# T03_MotionControledLampNFET.net
KiCad netlist of a schematic drawn in EAGLE
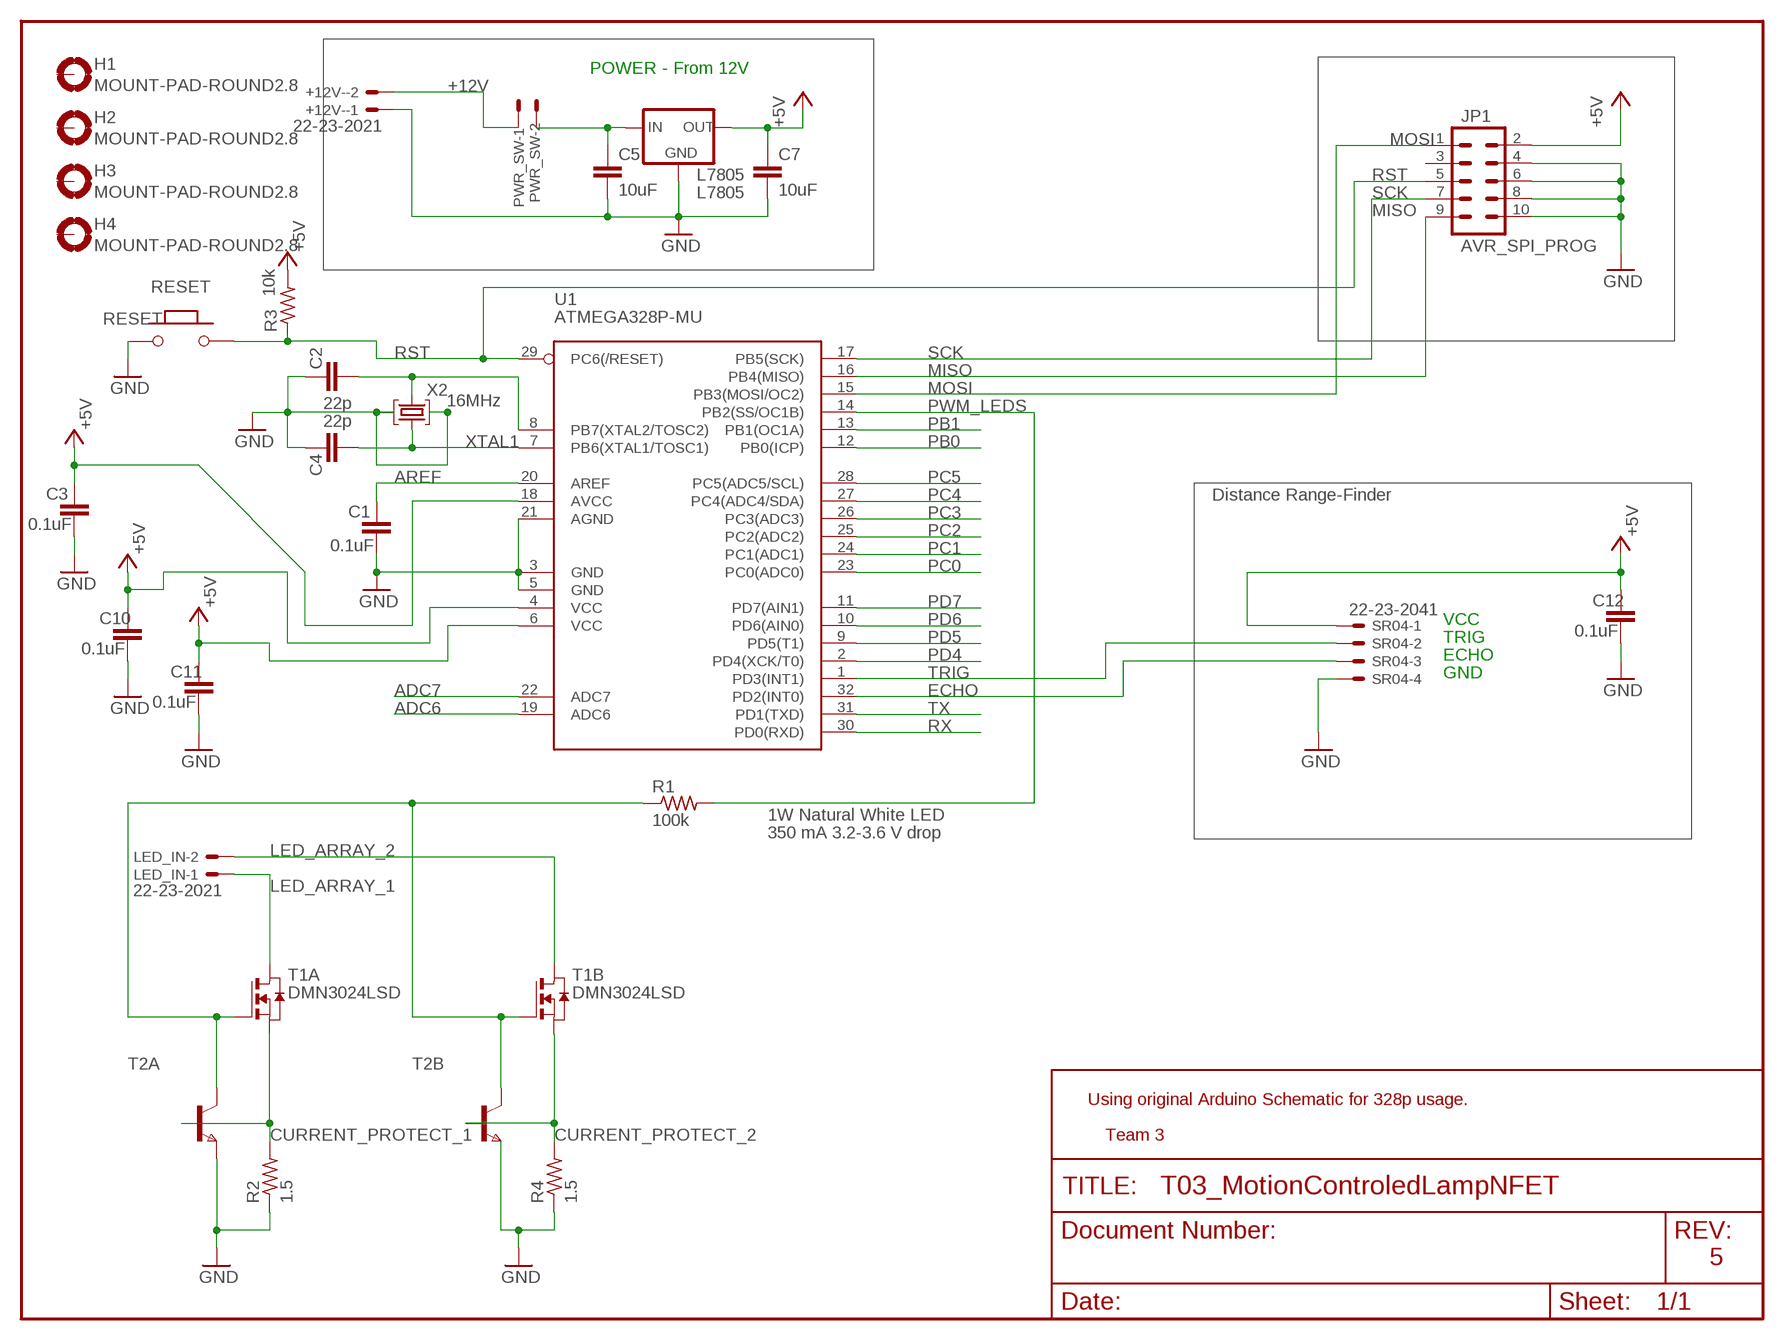
[diagram p0: schematic, sheet 1]

(export (version "E")
  (design (tool "Eeschema 10.0.6"))
  (components
    (comp (ref "+12V-")
      (value "22-23-2021")
      (footprint "eagle-import:22-23-2021")
      (fields (field (name "MF") "MOLEX"))
      (libsource (lib "eagle-import") (part "22-23-2021"))
    )
    (comp (ref "C1")
      (value "0.1uF")
      (footprint "eagle-import:C0603-ROUND")
      (libsource (lib "eagle-import") (part "C-EUC0603"))
    )
    (comp (ref "C2")
      (value "22p")
      (footprint "eagle-import:C0603-ROUND")
      (libsource (lib "eagle-import") (part "C-EUC0603"))
    )
    (comp (ref "C3")
      (value "0.1uF")
      (footprint "eagle-import:C0603-ROUND")
      (libsource (lib "eagle-import") (part "C-EUC0603"))
    )
    (comp (ref "C4")
      (value "22p")
      (footprint "eagle-import:C0603-ROUND")
      (libsource (lib "eagle-import") (part "C-EUC0603"))
    )
    (comp (ref "C5")
      (value "10uF")
      (footprint "eagle-import:C1206")
      (libsource (lib "eagle-import") (part "rcl_C-EUC1206"))
    )
    (comp (ref "C7")
      (value "10uF")
      (footprint "eagle-import:C1206")
      (libsource (lib "eagle-import") (part "rcl_C-EUC1206"))
    )
    (comp (ref "C10")
      (value "0.1uF")
      (footprint "eagle-import:C0603-ROUND")
      (libsource (lib "eagle-import") (part "C-EUC0603"))
    )
    (comp (ref "C11")
      (value "0.1uF")
      (footprint "eagle-import:C0603-ROUND")
      (libsource (lib "eagle-import") (part "C-EUC0603"))
    )
    (comp (ref "C12")
      (value "0.1uF")
      (footprint "eagle-import:C0603-ROUND")
      (libsource (lib "eagle-import") (part "C-EUC0603"))
    )
    (comp (ref "H1")
      (value "MOUNT-PAD-ROUND2.8")
      (footprint "eagle-import:2,8-PAD")
      (libsource (lib "eagle-import") (part "MOUNT-PAD-ROUND2.8"))
    )
    (comp (ref "H2")
      (value "MOUNT-PAD-ROUND2.8")
      (footprint "eagle-import:2,8-PAD")
      (libsource (lib "eagle-import") (part "MOUNT-PAD-ROUND2.8"))
    )
    (comp (ref "H3")
      (value "MOUNT-PAD-ROUND2.8")
      (footprint "eagle-import:2,8-PAD")
      (libsource (lib "eagle-import") (part "MOUNT-PAD-ROUND2.8"))
    )
    (comp (ref "H4")
      (value "MOUNT-PAD-ROUND2.8")
      (footprint "eagle-import:2,8-PAD")
      (libsource (lib "eagle-import") (part "MOUNT-PAD-ROUND2.8"))
    )
    (comp (ref "JP1")
      (value "AVR_SPI_PROG")
      (footprint "eagle-import:2X5-SHROUDED_LOCK")
      (libsource (lib "eagle-import") (part "M05X2SHD_LOCK"))
    )
    (comp (ref "L7805")
      (value "L7805")
      (footprint "eagle-import:78XXL")
      (libsource (lib "eagle-import") (part "78XXL"))
    )
    (comp (ref "LED_IN")
      (value "22-23-2021")
      (footprint "eagle-import:22-23-2021")
      (fields (field (name "MF") "MOLEX"))
      (libsource (lib "eagle-import") (part "22-23-2021"))
    )
    (comp (ref "PWR_SW")
      (value "22-23-2021")
      (footprint "eagle-import:22-23-2021")
      (fields (field (name "MF") "MOLEX"))
      (libsource (lib "eagle-import") (part "22-23-2021"))
    )
    (comp (ref "R1")
      (value "100k")
      (footprint "eagle-import:M1206")
      (libsource (lib "eagle-import") (part "R-US_M1206"))
    )
    (comp (ref "R2")
      (value "1.5")
      (footprint "eagle-import:M1206")
      (libsource (lib "eagle-import") (part "R-US_M1206"))
    )
    (comp (ref "R3")
      (value "10k")
      (footprint "eagle-import:M1206")
      (libsource (lib "eagle-import") (part "R-US_M1206"))
    )
    (comp (ref "R4")
      (value "1.5")
      (footprint "eagle-import:M1206")
      (libsource (lib "eagle-import") (part "R-US_M1206"))
    )
    (comp (ref "RESET")
      (value "RESET")
      (footprint "eagle-import:SMD_157SW")
      (libsource (lib "eagle-import") (part "MYSMD_PB157"))
    )
    (comp (ref "SR04")
      (value "22-23-2041")
      (footprint "eagle-import:22-23-2041")
      (fields (field (name "MF") "MOLEX"))
      (libsource (lib "eagle-import") (part "22-23-2041"))
    )
    (comp (ref "T1")
      (value "DMN3024LSD")
      (footprint "eagle-import:SO8")
      (libsource (lib "eagle-import") (part "DMN3024LSD"))
    )
    (comp (ref "T2")
      (value "NPNDUAL")
      (footprint "eagle-import:SM8")
      (libsource (lib "eagle-import") (part "NPNDUAL"))
    )
    (comp (ref "U1")
      (value "ATMEGA328P-MU")
      (footprint "eagle-import:TQFP32-08")
      (libsource (lib "eagle-import") (part "ATMEGAXX8-AU"))
    )
    (comp (ref "X2")
      (value "16MHz")
      (footprint "eagle-import:CRYSTAL-3.2-2.5")
      (libsource (lib "eagle-import") (part "CRYSTAL-3.2-2.5"))
    )
  )
  (nets
    (net (code "1") (name "+5V") (class "Default")
      (node (ref "C10") (pin "2") (pinfunction "2_2") (pintype "passive"))
      (node (ref "C11") (pin "2") (pinfunction "2_2") (pintype "passive"))
      (node (ref "C12") (pin "2") (pinfunction "2_2") (pintype "passive"))
      (node (ref "C3") (pin "2") (pinfunction "2_2") (pintype "passive"))
      (node (ref "C7") (pin "1") (pinfunction "1_1") (pintype "passive"))
      (node (ref "JP1") (pin "2") (pinfunction "2_2") (pintype "passive"))
      (node (ref "L7805") (pin "OUT") (pinfunction "OUT_OUT") (pintype "passive"))
      (node (ref "R3") (pin "2") (pinfunction "2_2") (pintype "passive"))
      (node (ref "SR04") (pin "1") (pinfunction "S_1") (pintype "passive"))
      (node (ref "U1") (pin "18") (pinfunction "AVCC_18") (pintype "bidirectional"))
      (node (ref "U1") (pin "4") (pinfunction "VCC_4") (pintype "bidirectional"))
      (node (ref "U1") (pin "6") (pinfunction "VCC_6") (pintype "bidirectional"))
    )
    (net (code "2") (name "/+12V") (class "Default")
      (node (ref "+12V-") (pin "2") (pinfunction "S_2") (pintype "passive"))
      (node (ref "PWR_SW") (pin "1") (pinfunction "S_1") (pintype "passive"))
    )
    (net (code "3") (name "/ADC6") (class "Default")
      (node (ref "U1") (pin "19") (pinfunction "ADC6_19") (pintype "bidirectional"))
    )
    (net (code "4") (name "/ADC7") (class "Default")
      (node (ref "U1") (pin "22") (pinfunction "ADC7_22") (pintype "bidirectional"))
    )
    (net (code "5") (name "/AREF") (class "Default")
      (node (ref "C1") (pin "2") (pinfunction "2_2") (pintype "passive"))
      (node (ref "U1") (pin "20") (pinfunction "AREF_20") (pintype "bidirectional"))
    )
    (net (code "6") (name "/CURRENT_PROTECT_1") (class "Default")
      (node (ref "R2") (pin "2") (pinfunction "2_2") (pintype "passive"))
      (node (ref "T1") (pin "1") (pinfunction "S_1") (pintype "passive"))
      (node (ref "T2") (pin "4") (pinfunction "B_4") (pintype "passive"))
    )
    (net (code "7") (name "/CURRENT_PROTECT_2") (class "Default")
      (node (ref "R4") (pin "2") (pinfunction "2_2") (pintype "passive"))
      (node (ref "T1") (pin "3") (pinfunction "S_3") (pintype "passive"))
      (node (ref "T2") (pin "2") (pinfunction "B_2") (pintype "passive"))
    )
    (net (code "8") (name "/ECHO") (class "Default")
      (node (ref "SR04") (pin "3") (pinfunction "S_3") (pintype "passive"))
      (node (ref "U1") (pin "32") (pinfunction "PD2(INT0)_32") (pintype "bidirectional"))
    )
    (net (code "9") (name "/LED_ARRAY_1") (class "Default")
      (node (ref "LED_IN") (pin "1") (pinfunction "S_1") (pintype "passive"))
      (node (ref "T1") (pin "7") (pinfunction "D_7") (pintype "passive"))
      (node (ref "T1") (pin "8") (pinfunction "D_8") (pintype "passive"))
    )
    (net (code "10") (name "/LED_ARRAY_2") (class "Default")
      (node (ref "LED_IN") (pin "2") (pinfunction "S_2") (pintype "passive"))
      (node (ref "T1") (pin "5") (pinfunction "D_5") (pintype "passive"))
      (node (ref "T1") (pin "6") (pinfunction "D_6") (pintype "passive"))
    )
    (net (code "11") (name "/MISO") (class "Default")
      (node (ref "JP1") (pin "9") (pinfunction "9_9") (pintype "passive"))
      (node (ref "U1") (pin "16") (pinfunction "PB4(MISO)_16") (pintype "bidirectional"))
    )
    (net (code "12") (name "/MOSI") (class "Default")
      (node (ref "JP1") (pin "1") (pinfunction "1_1") (pintype "passive"))
      (node (ref "U1") (pin "15") (pinfunction "PB3(MOSI/OC2)_15") (pintype "bidirectional"))
    )
    (net (code "13") (name "/PB0") (class "Default")
      (node (ref "U1") (pin "12") (pinfunction "PB0(ICP)_12") (pintype "bidirectional"))
    )
    (net (code "14") (name "/PB1") (class "Default")
      (node (ref "U1") (pin "13") (pinfunction "PB1(OC1A)_13") (pintype "bidirectional"))
    )
    (net (code "15") (name "/PC0") (class "Default")
      (node (ref "U1") (pin "23") (pinfunction "PC0(ADC0)_23") (pintype "bidirectional"))
    )
    (net (code "16") (name "/PC1") (class "Default")
      (node (ref "U1") (pin "24") (pinfunction "PC1(ADC1)_24") (pintype "bidirectional"))
    )
    (net (code "17") (name "/PC2") (class "Default")
      (node (ref "U1") (pin "25") (pinfunction "PC2(ADC2)_25") (pintype "bidirectional"))
    )
    (net (code "18") (name "/PC3") (class "Default")
      (node (ref "U1") (pin "26") (pinfunction "PC3(ADC3)_26") (pintype "bidirectional"))
    )
    (net (code "19") (name "/PC4") (class "Default")
      (node (ref "U1") (pin "27") (pinfunction "PC4(ADC4/SDA)_27") (pintype "bidirectional"))
    )
    (net (code "20") (name "/PC5") (class "Default")
      (node (ref "U1") (pin "28") (pinfunction "PC5(ADC5/SCL)_28") (pintype "bidirectional"))
    )
    (net (code "21") (name "/PD4") (class "Default")
      (node (ref "U1") (pin "2") (pinfunction "PD4(XCK/T0)_2") (pintype "bidirectional"))
    )
    (net (code "22") (name "/PD5") (class "Default")
      (node (ref "U1") (pin "9") (pinfunction "PD5(T1)_9") (pintype "bidirectional"))
    )
    (net (code "23") (name "/PD6") (class "Default")
      (node (ref "U1") (pin "10") (pinfunction "PD6(AIN0)_10") (pintype "bidirectional"))
    )
    (net (code "24") (name "/PD7") (class "Default")
      (node (ref "U1") (pin "11") (pinfunction "PD7(AIN1)_11") (pintype "bidirectional"))
    )
    (net (code "25") (name "/PWM_LEDS") (class "Default")
      (node (ref "R1") (pin "2") (pinfunction "2_2") (pintype "passive"))
      (node (ref "U1") (pin "14") (pinfunction "PB2(SS/OC1B)_14") (pintype "bidirectional"))
    )
    (net (code "26") (name "/RST") (class "Default")
      (node (ref "JP1") (pin "5") (pinfunction "5_5") (pintype "passive"))
      (node (ref "R3") (pin "1") (pinfunction "1_1") (pintype "passive"))
      (node (ref "RESET") (pin "2") (pinfunction "2_2") (pintype "passive"))
      (node (ref "U1") (pin "29") (pinfunction "PC6(/RESET)_29") (pintype "bidirectional"))
    )
    (net (code "27") (name "/RX") (class "Default")
      (node (ref "U1") (pin "30") (pinfunction "PD0(RXD)_30") (pintype "bidirectional"))
    )
    (net (code "28") (name "/SCK") (class "Default")
      (node (ref "JP1") (pin "7") (pinfunction "7_7") (pintype "passive"))
      (node (ref "U1") (pin "17") (pinfunction "PB5(SCK)_17") (pintype "bidirectional"))
    )
    (net (code "29") (name "/TRIG") (class "Default")
      (node (ref "SR04") (pin "2") (pinfunction "S_2") (pintype "passive"))
      (node (ref "U1") (pin "1") (pinfunction "PD3(INT1)_1") (pintype "bidirectional"))
    )
    (net (code "30") (name "/TX") (class "Default")
      (node (ref "U1") (pin "31") (pinfunction "PD1(TXD)_31") (pintype "bidirectional"))
    )
    (net (code "31") (name "/XTAL1") (class "Default")
      (node (ref "C4") (pin "1") (pinfunction "1_1") (pintype "passive"))
      (node (ref "U1") (pin "7") (pinfunction "PB6(XTAL1/TOSC1)_7") (pintype "bidirectional"))
      (node (ref "X2") (pin "1") (pinfunction "C1_1") (pintype "passive"))
    )
    (net (code "32") (name "GND") (class "Default")
      (node (ref "+12V-") (pin "1") (pinfunction "S_1") (pintype "passive"))
      (node (ref "C1") (pin "1") (pinfunction "1_1") (pintype "passive"))
      (node (ref "C10") (pin "1") (pinfunction "1_1") (pintype "passive"))
      (node (ref "C11") (pin "1") (pinfunction "1_1") (pintype "passive"))
      (node (ref "C12") (pin "1") (pinfunction "1_1") (pintype "passive"))
      (node (ref "C2") (pin "2") (pinfunction "2_2") (pintype "passive"))
      (node (ref "C3") (pin "1") (pinfunction "1_1") (pintype "passive"))
      (node (ref "C4") (pin "2") (pinfunction "2_2") (pintype "passive"))
      (node (ref "C5") (pin "2") (pinfunction "2_2") (pintype "passive"))
      (node (ref "C7") (pin "2") (pinfunction "2_2") (pintype "passive"))
      (node (ref "JP1") (pin "10") (pinfunction "10_10") (pintype "passive"))
      (node (ref "JP1") (pin "4") (pinfunction "4_4") (pintype "passive"))
      (node (ref "JP1") (pin "6") (pinfunction "6_6") (pintype "passive"))
      (node (ref "JP1") (pin "8") (pinfunction "8_8") (pintype "passive"))
      (node (ref "L7805") (pin "GND") (pinfunction "GND_GND") (pintype "input"))
      (node (ref "R2") (pin "1") (pinfunction "1_1") (pintype "passive"))
      (node (ref "R4") (pin "1") (pinfunction "1_1") (pintype "passive"))
      (node (ref "RESET") (pin "1") (pinfunction "1_1") (pintype "passive"))
      (node (ref "SR04") (pin "4") (pinfunction "S_4") (pintype "passive"))
      (node (ref "T2") (pin "3") (pinfunction "E_3") (pintype "passive"))
      (node (ref "U1") (pin "21") (pinfunction "AGND_21") (pintype "bidirectional"))
      (node (ref "U1") (pin "3") (pinfunction "GND_3") (pintype "bidirectional"))
      (node (ref "U1") (pin "5") (pinfunction "GND_5") (pintype "bidirectional"))
      (node (ref "X2") (pin "2") (pinfunction "GND_2") (pintype "passive"))
      (node (ref "X2") (pin "4") (pinfunction "GND_4") (pintype "passive"))
    )
    (net (code "33") (name "Net-(PWR_SWB-S)") (class "Default")
      (node (ref "C5") (pin "1") (pinfunction "1_1") (pintype "passive"))
      (node (ref "L7805") (pin "IN") (pinfunction "IN_IN") (pintype "input"))
      (node (ref "PWR_SW") (pin "2") (pinfunction "S_2") (pintype "passive"))
    )
    (net (code "34") (name "Net-(T1A-G)") (class "Default")
      (node (ref "R1") (pin "1") (pinfunction "1_1") (pintype "passive"))
      (node (ref "T1") (pin "2") (pinfunction "G_2") (pintype "passive"))
      (node (ref "T1") (pin "4") (pinfunction "G_4") (pintype "passive"))
      (node (ref "T2") (pin "5") (pinfunction "C_5") (pintype "passive"))
      (node (ref "T2") (pin "6") (pinfunction "C_6") (pintype "passive"))
      (node (ref "T2") (pin "7") (pinfunction "C_7") (pintype "passive"))
      (node (ref "T2") (pin "8") (pinfunction "C_8") (pintype "passive"))
    )
    (net (code "35") (name "Net-(U1-PB7(XTAL2{slash}TOSC2))") (class "Default")
      (node (ref "C2") (pin "1") (pinfunction "1_1") (pintype "passive"))
      (node (ref "U1") (pin "8") (pinfunction "PB7(XTAL2/TOSC2)_8") (pintype "bidirectional"))
      (node (ref "X2") (pin "3") (pinfunction "C2_3") (pintype "passive"))
    )
    (net (code "36") (name "unconnected-(H1-MOUNT-PadB2,8)") (class "Default")
      (node (ref "H1") (pin "B2,8") (pinfunction "MOUNT_B2,8") (pintype "passive"))
    )
    (net (code "37") (name "unconnected-(H2-MOUNT-PadB2,8)") (class "Default")
      (node (ref "H2") (pin "B2,8") (pinfunction "MOUNT_B2,8") (pintype "passive"))
    )
    (net (code "38") (name "unconnected-(H3-MOUNT-PadB2,8)") (class "Default")
      (node (ref "H3") (pin "B2,8") (pinfunction "MOUNT_B2,8") (pintype "passive"))
    )
    (net (code "39") (name "unconnected-(H4-MOUNT-PadB2,8)") (class "Default")
      (node (ref "H4") (pin "B2,8") (pinfunction "MOUNT_B2,8") (pintype "passive"))
    )
    (net (code "40") (name "unconnected-(JP1-Pad3)") (class "Default")
      (node (ref "JP1") (pin "3") (pinfunction "3_3") (pintype "passive"))
    )
    (net (code "41") (name "unconnected-(T2B-E-Pad1)") (class "Default")
      (node (ref "T2") (pin "1") (pinfunction "E_1") (pintype "passive"))
    )
  )
)
